# Vattenkran.net
KiCad netlist of a schematic drawn in EAGLE
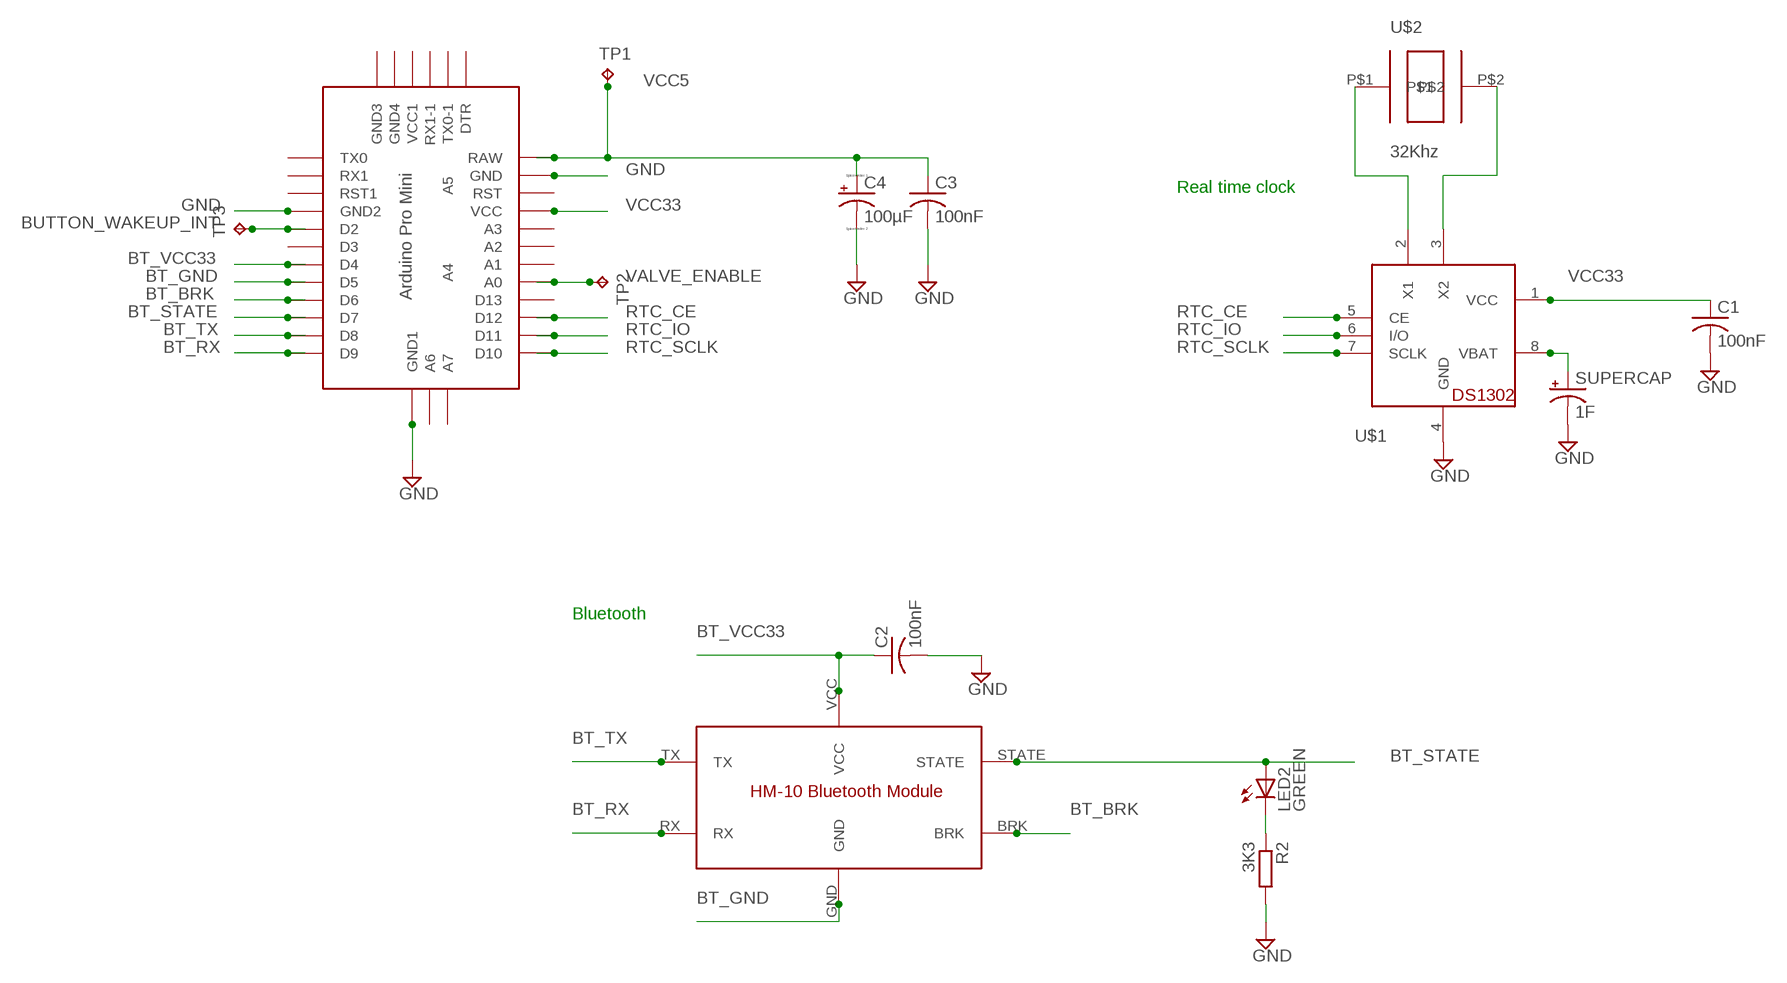
[diagram p0: schematic, sheet 1]

(export (version "E")
  (design (tool "Eeschema 10.0.6"))
  (components
    (comp (ref "C1")
      (value "100nF")
      (footprint "eagle-import:C0805")
      (libsource (lib "eagle-import") (part "C-USC0805"))
    )
    (comp (ref "C2")
      (value "100nF")
      (footprint "eagle-import:C0805")
      (libsource (lib "eagle-import") (part "C-USC0805"))
    )
    (comp (ref "C3")
      (value "100nF")
      (footprint "eagle-import:C0805")
      (libsource (lib "eagle-import") (part "C-USC0805"))
    )
    (comp (ref "C4")
      (value "100µF")
      (footprint "eagle-import:PANASONIC_D")
      (libsource (lib "eagle-import") (part "resistor_348_CPOL-USD"))
    )
    (comp (ref "LED2")
      (value "GREEN")
      (footprint "eagle-import:LED3MM")
      (libsource (lib "eagle-import") (part "LED3MM"))
    )
    (comp (ref "R2")
      (value "3K3")
      (footprint "eagle-import:R0805")
      (libsource (lib "eagle-import") (part "R-EU_R0805"))
    )
    (comp (ref "SUPERCAP")
      (value "1F")
      (footprint "eagle-import:ETR2")
      (libsource (lib "eagle-import") (part "CPOL-USETR2"))
    )
    (comp (ref "TP1")
      (value "TPB1,27")
      (footprint "eagle-import:B1,27")
      (libsource (lib "eagle-import") (part "TPB1,27"))
    )
    (comp (ref "TP2")
      (value "TPB1,27")
      (footprint "eagle-import:B1,27")
      (libsource (lib "eagle-import") (part "TPB1,27"))
    )
    (comp (ref "TP3")
      (value "TPB1,27")
      (footprint "eagle-import:B1,27")
      (libsource (lib "eagle-import") (part "TPB1,27"))
    )
    (comp (ref "U$1")
      (value "DS1302")
      (footprint "eagle-import:SOP8")
      (libsource (lib "eagle-import") (part "DS1302"))
    )
    (comp (ref "U$2")
      (value "32Khz")
      (footprint "eagle-import:SM3")
      (libsource (lib "eagle-import") (part "CLOCK_CRYSTAL_32KHZ"))
    )
    (comp (ref "U$4")
      (value "HM10_BLUETOOTH_MODULE")
      (footprint "eagle-import:HM10_BLUETOOTH_MODULE")
      (libsource (lib "eagle-import") (part "HM10_BLUETOOTH_MODULE"))
    )
    (comp (ref "U$7")
      (value "ABK-PRO-MINI")
      (footprint "eagle-import:ABK-PRO-MINI")
      (libsource (lib "eagle-import") (part "ABK-PRO-MINI"))
    )
  )
  (nets
    (net (code "1") (name "/BT_BRK") (class "Default")
      (node (ref "U$4") (pin "BRK") (pinfunction "BRK_BRK") (pintype "input"))
      (node (ref "U$7") (pin "D6") (pinfunction "D6_D6") (pintype "bidirectional"))
    )
    (net (code "2") (name "/BT_GND") (class "Default")
      (node (ref "U$4") (pin "GND") (pinfunction "GND_GND") (pintype "power_in"))
      (node (ref "U$7") (pin "D5") (pinfunction "D5_D5") (pintype "bidirectional"))
    )
    (net (code "3") (name "/BT_RX") (class "Default")
      (node (ref "U$4") (pin "RX") (pinfunction "RX_RX") (pintype "bidirectional"))
      (node (ref "U$7") (pin "D9") (pinfunction "D9_D9") (pintype "bidirectional"))
    )
    (net (code "4") (name "/BT_STATE") (class "Default")
      (node (ref "LED2") (pin "A") (pinfunction "A_A") (pintype "passive"))
      (node (ref "U$4") (pin "STATE") (pinfunction "STATE_STATE") (pintype "output"))
      (node (ref "U$7") (pin "D7") (pinfunction "D7_D7") (pintype "bidirectional"))
    )
    (net (code "5") (name "/BT_TX") (class "Default")
      (node (ref "U$4") (pin "TX") (pinfunction "TX_TX") (pintype "bidirectional"))
      (node (ref "U$7") (pin "D8") (pinfunction "D8_D8") (pintype "bidirectional"))
    )
    (net (code "6") (name "/BT_VCC33") (class "Default")
      (node (ref "C2") (pin "1") (pinfunction "1_1") (pintype "passive"))
      (node (ref "U$4") (pin "VCC") (pinfunction "VCC_VCC") (pintype "power_in"))
      (node (ref "U$7") (pin "D4") (pinfunction "D4_D4") (pintype "bidirectional"))
    )
    (net (code "7") (name "/BUTTON_WAKEUP_INT") (class "Default")
      (node (ref "TP3") (pin "TP") (pinfunction "TP_TP") (pintype "input"))
      (node (ref "U$7") (pin "D2") (pinfunction "D2_D2") (pintype "bidirectional"))
    )
    (net (code "8") (name "/RTC_CE") (class "Default")
      (node (ref "U$1") (pin "5") (pinfunction "CE_5") (pintype "input"))
      (node (ref "U$7") (pin "D12") (pinfunction "D12_D12") (pintype "bidirectional"))
    )
    (net (code "9") (name "/RTC_IO") (class "Default")
      (node (ref "U$1") (pin "6") (pinfunction "I/O_6") (pintype "bidirectional"))
      (node (ref "U$7") (pin "D11") (pinfunction "D11_D11") (pintype "bidirectional"))
    )
    (net (code "10") (name "/RTC_SCLK") (class "Default")
      (node (ref "U$1") (pin "7") (pinfunction "SCLK_7") (pintype "input"))
      (node (ref "U$7") (pin "D10") (pinfunction "D10_D10") (pintype "bidirectional"))
    )
    (net (code "11") (name "/VALVE_ENABLE") (class "Default")
      (node (ref "TP2") (pin "TP") (pinfunction "TP_TP") (pintype "input"))
      (node (ref "U$7") (pin "A0") (pinfunction "A0_A0") (pintype "bidirectional"))
    )
    (net (code "12") (name "/VCC5") (class "Default")
      (node (ref "C3") (pin "1") (pinfunction "1_1") (pintype "passive"))
      (node (ref "C4") (pin "+") (pinfunction "+_+") (pintype "passive"))
      (node (ref "TP1") (pin "TP") (pinfunction "TP_TP") (pintype "input"))
      (node (ref "U$7") (pin "RAW") (pinfunction "RAW_RAW") (pintype "bidirectional"))
    )
    (net (code "13") (name "/VCC33") (class "Default")
      (node (ref "C1") (pin "1") (pinfunction "1_1") (pintype "passive"))
      (node (ref "U$1") (pin "1") (pinfunction "VCC_1") (pintype "power_in"))
      (node (ref "U$7") (pin "VCC") (pinfunction "VCC_VCC") (pintype "bidirectional"))
    )
    (net (code "14") (name "GND") (class "Default")
      (node (ref "C1") (pin "2") (pinfunction "2_2") (pintype "passive"))
      (node (ref "C2") (pin "2") (pinfunction "2_2") (pintype "passive"))
      (node (ref "C3") (pin "2") (pinfunction "2_2") (pintype "passive"))
      (node (ref "C4") (pin "-") (pinfunction "-_-") (pintype "passive"))
      (node (ref "R2") (pin "2") (pinfunction "2_2") (pintype "passive"))
      (node (ref "SUPERCAP") (pin "-") (pinfunction "-_-") (pintype "passive"))
      (node (ref "U$1") (pin "4") (pinfunction "GND_4") (pintype "power_in"))
      (node (ref "U$7") (pin "GND") (pinfunction "GND_GND") (pintype "bidirectional"))
      (node (ref "U$7") (pin "GND1") (pinfunction "GND2_GND1") (pintype "bidirectional"))
      (node (ref "U$7") (pin "GND4") (pinfunction "GND1_GND4") (pintype "bidirectional"))
    )
    (net (code "15") (name "Net-(LED2-C)") (class "Default")
      (node (ref "LED2") (pin "K") (pinfunction "C_K") (pintype "passive"))
      (node (ref "R2") (pin "1") (pinfunction "1_1") (pintype "passive"))
    )
    (net (code "16") (name "Net-(U$1-VBAT)") (class "Default")
      (node (ref "SUPERCAP") (pin "+") (pinfunction "+_+") (pintype "passive"))
      (node (ref "U$1") (pin "8") (pinfunction "VBAT_8") (pintype "power_in"))
    )
    (net (code "17") (name "Net-(U$1-X1)") (class "Default")
      (node (ref "U$1") (pin "2") (pinfunction "X1_2") (pintype "passive"))
      (node (ref "U$2") (pin "P$1") (pinfunction "P$1_P$1") (pintype "bidirectional"))
    )
    (net (code "18") (name "Net-(U$1-X2)") (class "Default")
      (node (ref "U$1") (pin "3") (pinfunction "X2_3") (pintype "passive"))
      (node (ref "U$2") (pin "P$2") (pinfunction "P$2_P$2") (pintype "bidirectional"))
    )
    (net (code "19") (name "unconnected-(U$7-GND3-PadGND2)") (class "Default")
      (node (ref "U$7") (pin "GND2") (pinfunction "GND3_GND2") (pintype "bidirectional"))
    )
    (net (code "20") (name "unconnected-(U$7-GND4-PadGND3)") (class "Default")
      (node (ref "U$7") (pin "GND3") (pinfunction "GND4_GND3") (pintype "bidirectional"))
    )
    (net (code "21") (name "unconnected-(U$7-PadA1)") (class "Default")
      (node (ref "U$7") (pin "A1") (pinfunction "A1_A1") (pintype "bidirectional"))
    )
    (net (code "22") (name "unconnected-(U$7-PadA2)") (class "Default")
      (node (ref "U$7") (pin "A2") (pinfunction "A2_A2") (pintype "bidirectional"))
    )
    (net (code "23") (name "unconnected-(U$7-PadA3)") (class "Default")
      (node (ref "U$7") (pin "A3") (pinfunction "A3_A3") (pintype "bidirectional"))
    )
    (net (code "24") (name "unconnected-(U$7-PadA4)") (class "Default")
      (node (ref "U$7") (pin "A4") (pinfunction "A4_A4") (pintype "bidirectional"))
    )
    (net (code "25") (name "unconnected-(U$7-PadA5)") (class "Default")
      (node (ref "U$7") (pin "A5") (pinfunction "A5_A5") (pintype "bidirectional"))
    )
    (net (code "26") (name "unconnected-(U$7-PadA6)") (class "Default")
      (node (ref "U$7") (pin "A6") (pinfunction "A6_A6") (pintype "bidirectional"))
    )
    (net (code "27") (name "unconnected-(U$7-PadA7)") (class "Default")
      (node (ref "U$7") (pin "A7") (pinfunction "A7_A7") (pintype "bidirectional"))
    )
    (net (code "28") (name "unconnected-(U$7-PadD3)") (class "Default")
      (node (ref "U$7") (pin "D3") (pinfunction "D3_D3") (pintype "bidirectional"))
    )
    (net (code "29") (name "unconnected-(U$7-PadD13)") (class "Default")
      (node (ref "U$7") (pin "D13") (pinfunction "D13_D13") (pintype "bidirectional"))
    )
    (net (code "30") (name "unconnected-(U$7-PadDTR)") (class "Default")
      (node (ref "U$7") (pin "DTR") (pinfunction "DTR_DTR") (pintype "bidirectional"))
    )
    (net (code "31") (name "unconnected-(U$7-PadRST)") (class "Default")
      (node (ref "U$7") (pin "RST") (pinfunction "RST_RST") (pintype "bidirectional"))
    )
    (net (code "32") (name "unconnected-(U$7-PadRST1)") (class "Default")
      (node (ref "U$7") (pin "RST1") (pinfunction "RST1_RST1") (pintype "bidirectional"))
    )
    (net (code "33") (name "unconnected-(U$7-PadRX1)") (class "Default")
      (node (ref "U$7") (pin "RX1") (pinfunction "RX1_RX1") (pintype "bidirectional"))
    )
    (net (code "34") (name "unconnected-(U$7-PadRX1-1)") (class "Default")
      (node (ref "U$7") (pin "RX1-1") (pinfunction "RX1-1_RX1-1") (pintype "bidirectional"))
    )
    (net (code "35") (name "unconnected-(U$7-PadTX0)") (class "Default")
      (node (ref "U$7") (pin "TX0") (pinfunction "TX0_TX0") (pintype "bidirectional"))
    )
    (net (code "36") (name "unconnected-(U$7-PadTX0-1)") (class "Default")
      (node (ref "U$7") (pin "TX0-1") (pinfunction "TX0-1_TX0-1") (pintype "bidirectional"))
    )
    (net (code "37") (name "unconnected-(U$7-PadVCC1)") (class "Default")
      (node (ref "U$7") (pin "VCC1") (pinfunction "VCC1_VCC1") (pintype "bidirectional"))
    )
  )
)
